# MCU.net
KiCad netlist of a schematic drawn in Altium Designer
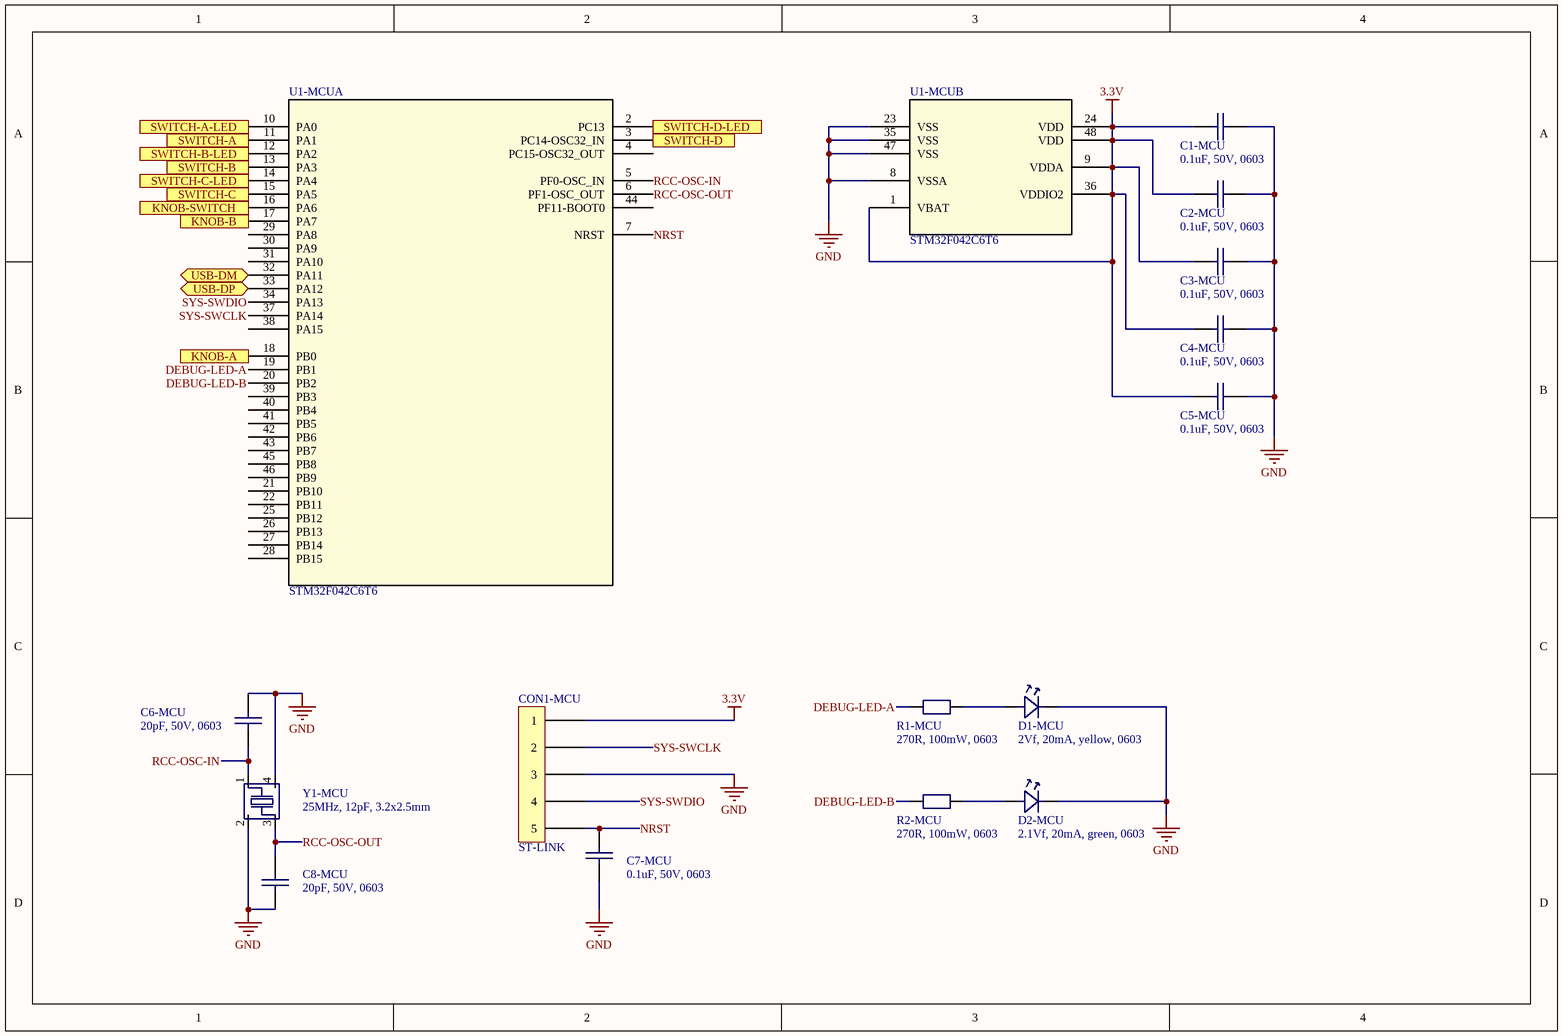
[diagram p0: MCU.SchDoc]

(export (version "E")
  (design (tool "Eeschema 10.0.6"))
  (components
    (comp (ref "C1-MCU")
      (value "0.1uF, 50V, 0603")
      (footprint "0603 [1608]")
      (fields (field (name "MANUFACTURER") "MULTICOMP PRO"))
      (libsource (lib "SCH-LIB") (part "Capacitor"))
    )
    (comp (ref "C2-MCU")
      (value "0.1uF, 50V, 0603")
      (footprint "0603 [1608]")
      (fields (field (name "MANUFACTURER") "MULTICOMP PRO"))
      (libsource (lib "SCH-LIB") (part "Capacitor"))
    )
    (comp (ref "C3-MCU")
      (value "0.1uF, 50V, 0603")
      (footprint "0603 [1608]")
      (fields (field (name "MANUFACTURER") "MULTICOMP PRO"))
      (libsource (lib "SCH-LIB") (part "Capacitor"))
    )
    (comp (ref "C4-MCU")
      (value "0.1uF, 50V, 0603")
      (footprint "0603 [1608]")
      (fields (field (name "MANUFACTURER") "MULTICOMP PRO"))
      (libsource (lib "SCH-LIB") (part "Capacitor"))
    )
    (comp (ref "C5-MCU")
      (value "0.1uF, 50V, 0603")
      (footprint "0603 [1608]")
      (fields (field (name "MANUFACTURER") "MULTICOMP PRO"))
      (libsource (lib "SCH-LIB") (part "Capacitor"))
    )
    (comp (ref "C6-MCU")
      (value "20pF, 50V, 0603")
      (footprint "0603 [1608]")
      (fields (field (name "MANUFACTURER") "MULTICOMP PRO"))
      (libsource (lib "SCH-LIB") (part "Capacitor"))
    )
    (comp (ref "C7-MCU")
      (value "0.1uF, 50V, 0603")
      (footprint "0603 [1608]")
      (fields (field (name "MANUFACTURER") "MULTICOMP PRO"))
      (libsource (lib "SCH-LIB") (part "Capacitor"))
    )
    (comp (ref "C8-MCU")
      (value "20pF, 50V, 0603")
      (footprint "0603 [1608]")
      (fields (field (name "MANUFACTURER") "MULTICOMP PRO"))
      (libsource (lib "SCH-LIB") (part "Capacitor"))
    )
    (comp (ref "CON1-MCU")
      (value "ST-LINK")
      (footprint "5x1 Pin Header (TH)")
      (fields (field (name "MANUFACTURER") "AMPHENOL"))
      (libsource (lib "SCH-LIB") (part "5x1 Pin Header"))
    )
    (comp (ref "D1-MCU")
      (value "2Vf, 20mA, yellow, 0603")
      (footprint "LED 0603 [1608]")
      (fields (field (name "MANUFACTURER") "KINGBRIGHT"))
      (libsource (lib "SCH-LIB") (part "LED"))
    )
    (comp (ref "D2-MCU")
      (value "2.1Vf, 20mA, green, 0603")
      (footprint "LED 0603 [1608]")
      (fields (field (name "MANUFACTURER") "KINGBRIGHT"))
      (libsource (lib "SCH-LIB") (part "LED"))
    )
    (comp (ref "R1-MCU")
      (value "270R, 100mW, 0603")
      (footprint "0603 [1608]")
      (fields (field (name "MANUFACTURER") "YAGEO"))
      (libsource (lib "SCH-LIB") (part "Resistor"))
    )
    (comp (ref "R2-MCU")
      (value "270R, 100mW, 0603")
      (footprint "0603 [1608]")
      (fields (field (name "MANUFACTURER") "YAGEO"))
      (libsource (lib "SCH-LIB") (part "Resistor"))
    )
    (comp (ref "U1-MCU")
      (value "STM32F042C6T6")
      (footprint "LQFP48")
      (fields (field (name "MANUFACTURER") "STMicroelectronics"))
      (libsource (lib "SCH-LIB") (part "STM32F042C6T6 (MCU)"))
    )
    (comp (ref "Y1-MCU")
      (value "25MHz, 12pF, 3.2x2.5mm")
      (footprint "Crystal 3.2x2.5mm")
      (fields (field (name "MANUFACTURER") "MULTICOMP PRO"))
      (libsource (lib "SCH-LIB") (part "Crystal 4-pin"))
    )
  )
  (nets
    (net (code "1") (name "/DEBUG-LED-A") (class "Default")
      (node (ref "R1-MCU") (pin "2") (pinfunction "2_2") (pintype "passive"))
      (node (ref "U1-MCU") (pin "19") (pinfunction "PB1_19") (pintype "passive"))
    )
    (net (code "2") (name "/DEBUG-LED-B") (class "Default")
      (node (ref "R2-MCU") (pin "2") (pinfunction "2_2") (pintype "passive"))
      (node (ref "U1-MCU") (pin "20") (pinfunction "PB2_20") (pintype "passive"))
    )
    (net (code "3") (name "/KNOB-A") (class "Default")
      (node (ref "U1-MCU") (pin "18") (pinfunction "PB0_18") (pintype "passive"))
    )
    (net (code "4") (name "/KNOB-B") (class "Default")
      (node (ref "U1-MCU") (pin "17") (pinfunction "PA7_17") (pintype "passive"))
    )
    (net (code "5") (name "/KNOB-SWITCH") (class "Default")
      (node (ref "U1-MCU") (pin "16") (pinfunction "PA6_16") (pintype "passive"))
    )
    (net (code "6") (name "/NRST") (class "Default")
      (node (ref "C7-MCU") (pin "1") (pinfunction "1_1") (pintype "passive"))
      (node (ref "CON1-MCU") (pin "5") (pinfunction "5_5") (pintype "passive"))
      (node (ref "U1-MCU") (pin "7") (pinfunction "NRST_7") (pintype "passive"))
    )
    (net (code "7") (name "/RCC-OSC-IN") (class "Default")
      (node (ref "C6-MCU") (pin "2") (pinfunction "2_2") (pintype "passive"))
      (node (ref "U1-MCU") (pin "5") (pinfunction "PF0-OSC_IN_5") (pintype "passive"))
      (node (ref "Y1-MCU") (pin "1") (pinfunction "1_1") (pintype "passive"))
    )
    (net (code "8") (name "/RCC-OSC-OUT") (class "Default")
      (node (ref "C8-MCU") (pin "1") (pinfunction "1_1") (pintype "passive"))
      (node (ref "U1-MCU") (pin "6") (pinfunction "PF1-OSC_OUT_6") (pintype "passive"))
      (node (ref "Y1-MCU") (pin "3") (pinfunction "3_3") (pintype "passive"))
    )
    (net (code "9") (name "/SWITCH-A") (class "Default")
      (node (ref "U1-MCU") (pin "11") (pinfunction "PA1_11") (pintype "passive"))
    )
    (net (code "10") (name "/SWITCH-A-LED") (class "Default")
      (node (ref "U1-MCU") (pin "10") (pinfunction "PA0_10") (pintype "passive"))
    )
    (net (code "11") (name "/SWITCH-B") (class "Default")
      (node (ref "U1-MCU") (pin "13") (pinfunction "PA3_13") (pintype "passive"))
    )
    (net (code "12") (name "/SWITCH-B-LED") (class "Default")
      (node (ref "U1-MCU") (pin "12") (pinfunction "PA2_12") (pintype "passive"))
    )
    (net (code "13") (name "/SWITCH-C") (class "Default")
      (node (ref "U1-MCU") (pin "15") (pinfunction "PA5_15") (pintype "passive"))
    )
    (net (code "14") (name "/SWITCH-C-LED") (class "Default")
      (node (ref "U1-MCU") (pin "14") (pinfunction "PA4_14") (pintype "passive"))
    )
    (net (code "15") (name "/SWITCH-D") (class "Default")
      (node (ref "U1-MCU") (pin "3") (pinfunction "PC14-OSC32_IN_3") (pintype "passive"))
    )
    (net (code "16") (name "/SWITCH-D-LED") (class "Default")
      (node (ref "U1-MCU") (pin "2") (pinfunction "PC13_2") (pintype "passive"))
    )
    (net (code "17") (name "/SYS-SWCLK") (class "Default")
      (node (ref "CON1-MCU") (pin "2") (pinfunction "2_2") (pintype "passive"))
      (node (ref "U1-MCU") (pin "37") (pinfunction "PA14_37") (pintype "passive"))
    )
    (net (code "18") (name "/SYS-SWDIO") (class "Default")
      (node (ref "CON1-MCU") (pin "4") (pinfunction "4_4") (pintype "passive"))
      (node (ref "U1-MCU") (pin "34") (pinfunction "PA13_34") (pintype "passive"))
    )
    (net (code "19") (name "/USB-DM") (class "Default")
      (node (ref "U1-MCU") (pin "32") (pinfunction "PA11_32") (pintype "passive"))
    )
    (net (code "20") (name "/USB-DP") (class "Default")
      (node (ref "U1-MCU") (pin "33") (pinfunction "PA12_33") (pintype "passive"))
    )
    (net (code "21") (name "3.3V") (class "Default")
      (node (ref "C1-MCU") (pin "1") (pinfunction "1_1") (pintype "passive"))
      (node (ref "C2-MCU") (pin "1") (pinfunction "1_1") (pintype "passive"))
      (node (ref "C3-MCU") (pin "1") (pinfunction "1_1") (pintype "passive"))
      (node (ref "C4-MCU") (pin "1") (pinfunction "1_1") (pintype "passive"))
      (node (ref "C5-MCU") (pin "1") (pinfunction "1_1") (pintype "passive"))
      (node (ref "CON1-MCU") (pin "1") (pinfunction "1_1") (pintype "passive"))
      (node (ref "U1-MCU") (pin "1") (pinfunction "VBAT_1") (pintype "power_in"))
      (node (ref "U1-MCU") (pin "24") (pinfunction "VDD_24") (pintype "power_in"))
      (node (ref "U1-MCU") (pin "36") (pinfunction "VDDIO2_36") (pintype "power_in"))
      (node (ref "U1-MCU") (pin "48") (pinfunction "VDD_48") (pintype "power_in"))
      (node (ref "U1-MCU") (pin "9") (pinfunction "VDDA_9") (pintype "power_in"))
    )
    (net (code "22") (name "GND") (class "Default")
      (node (ref "C1-MCU") (pin "2") (pinfunction "2_2") (pintype "passive"))
      (node (ref "C2-MCU") (pin "2") (pinfunction "2_2") (pintype "passive"))
      (node (ref "C3-MCU") (pin "2") (pinfunction "2_2") (pintype "passive"))
      (node (ref "C4-MCU") (pin "2") (pinfunction "2_2") (pintype "passive"))
      (node (ref "C5-MCU") (pin "2") (pinfunction "2_2") (pintype "passive"))
      (node (ref "C6-MCU") (pin "1") (pinfunction "1_1") (pintype "passive"))
      (node (ref "C7-MCU") (pin "2") (pinfunction "2_2") (pintype "passive"))
      (node (ref "C8-MCU") (pin "2") (pinfunction "2_2") (pintype "passive"))
      (node (ref "CON1-MCU") (pin "3") (pinfunction "3_3") (pintype "passive"))
      (node (ref "D1-MCU") (pin "1") (pinfunction "1_1") (pintype "passive"))
      (node (ref "D2-MCU") (pin "1") (pinfunction "1_1") (pintype "passive"))
      (node (ref "U1-MCU") (pin "23") (pinfunction "VSS_23") (pintype "power_in"))
      (node (ref "U1-MCU") (pin "35") (pinfunction "VSS_35") (pintype "power_in"))
      (node (ref "U1-MCU") (pin "47") (pinfunction "VSS_47") (pintype "power_in"))
      (node (ref "U1-MCU") (pin "8") (pinfunction "VSSA_8") (pintype "power_in"))
      (node (ref "Y1-MCU") (pin "2") (pinfunction "2_2") (pintype "passive"))
      (node (ref "Y1-MCU") (pin "4") (pinfunction "4_4") (pintype "passive"))
    )
    (net (code "23") (name "Net-(D1-MCU-Pad2)") (class "Default")
      (node (ref "D1-MCU") (pin "2") (pinfunction "2_2") (pintype "passive"))
      (node (ref "R1-MCU") (pin "1") (pinfunction "1_1") (pintype "passive"))
    )
    (net (code "24") (name "Net-(D2-MCU-Pad2)") (class "Default")
      (node (ref "D2-MCU") (pin "2") (pinfunction "2_2") (pintype "passive"))
      (node (ref "R2-MCU") (pin "1") (pinfunction "1_1") (pintype "passive"))
    )
    (net (code "25") (name "unconnected-(U1-MCUA-PA8-Pad29)") (class "Default")
      (node (ref "U1-MCU") (pin "29") (pinfunction "PA8_29") (pintype "passive"))
    )
    (net (code "26") (name "unconnected-(U1-MCUA-PA9-Pad30)") (class "Default")
      (node (ref "U1-MCU") (pin "30") (pinfunction "PA9_30") (pintype "passive"))
    )
    (net (code "27") (name "unconnected-(U1-MCUA-PA10-Pad31)") (class "Default")
      (node (ref "U1-MCU") (pin "31") (pinfunction "PA10_31") (pintype "passive"))
    )
    (net (code "28") (name "unconnected-(U1-MCUA-PA15-Pad38)") (class "Default")
      (node (ref "U1-MCU") (pin "38") (pinfunction "PA15_38") (pintype "passive"))
    )
    (net (code "29") (name "unconnected-(U1-MCUA-PB3-Pad39)") (class "Default")
      (node (ref "U1-MCU") (pin "39") (pinfunction "PB3_39") (pintype "passive"))
    )
    (net (code "30") (name "unconnected-(U1-MCUA-PB4-Pad40)") (class "Default")
      (node (ref "U1-MCU") (pin "40") (pinfunction "PB4_40") (pintype "passive"))
    )
    (net (code "31") (name "unconnected-(U1-MCUA-PB5-Pad41)") (class "Default")
      (node (ref "U1-MCU") (pin "41") (pinfunction "PB5_41") (pintype "passive"))
    )
    (net (code "32") (name "unconnected-(U1-MCUA-PB6-Pad42)") (class "Default")
      (node (ref "U1-MCU") (pin "42") (pinfunction "PB6_42") (pintype "passive"))
    )
    (net (code "33") (name "unconnected-(U1-MCUA-PB7-Pad43)") (class "Default")
      (node (ref "U1-MCU") (pin "43") (pinfunction "PB7_43") (pintype "passive"))
    )
    (net (code "34") (name "unconnected-(U1-MCUA-PB8-Pad45)") (class "Default")
      (node (ref "U1-MCU") (pin "45") (pinfunction "PB8_45") (pintype "passive"))
    )
    (net (code "35") (name "unconnected-(U1-MCUA-PB9-Pad46)") (class "Default")
      (node (ref "U1-MCU") (pin "46") (pinfunction "PB9_46") (pintype "passive"))
    )
    (net (code "36") (name "unconnected-(U1-MCUA-PB10-Pad21)") (class "Default")
      (node (ref "U1-MCU") (pin "21") (pinfunction "PB10_21") (pintype "passive"))
    )
    (net (code "37") (name "unconnected-(U1-MCUA-PB11-Pad22)") (class "Default")
      (node (ref "U1-MCU") (pin "22") (pinfunction "PB11_22") (pintype "passive"))
    )
    (net (code "38") (name "unconnected-(U1-MCUA-PB12-Pad25)") (class "Default")
      (node (ref "U1-MCU") (pin "25") (pinfunction "PB12_25") (pintype "passive"))
    )
    (net (code "39") (name "unconnected-(U1-MCUA-PB13-Pad26)") (class "Default")
      (node (ref "U1-MCU") (pin "26") (pinfunction "PB13_26") (pintype "passive"))
    )
    (net (code "40") (name "unconnected-(U1-MCUA-PB14-Pad27)") (class "Default")
      (node (ref "U1-MCU") (pin "27") (pinfunction "PB14_27") (pintype "passive"))
    )
    (net (code "41") (name "unconnected-(U1-MCUA-PB15-Pad28)") (class "Default")
      (node (ref "U1-MCU") (pin "28") (pinfunction "PB15_28") (pintype "passive"))
    )
    (net (code "42") (name "unconnected-(U1-MCUA-PC15-OSC32_OUT-Pad4)") (class "Default")
      (node (ref "U1-MCU") (pin "4") (pinfunction "PC15-OSC32_OUT_4") (pintype "passive"))
    )
    (net (code "43") (name "unconnected-(U1-MCUA-PF11-BOOT0-Pad44)") (class "Default")
      (node (ref "U1-MCU") (pin "44") (pinfunction "PF11-BOOT0_44") (pintype "passive"))
    )
  )
)
